# v01.net
KiCad netlist of a schematic drawn in EAGLE
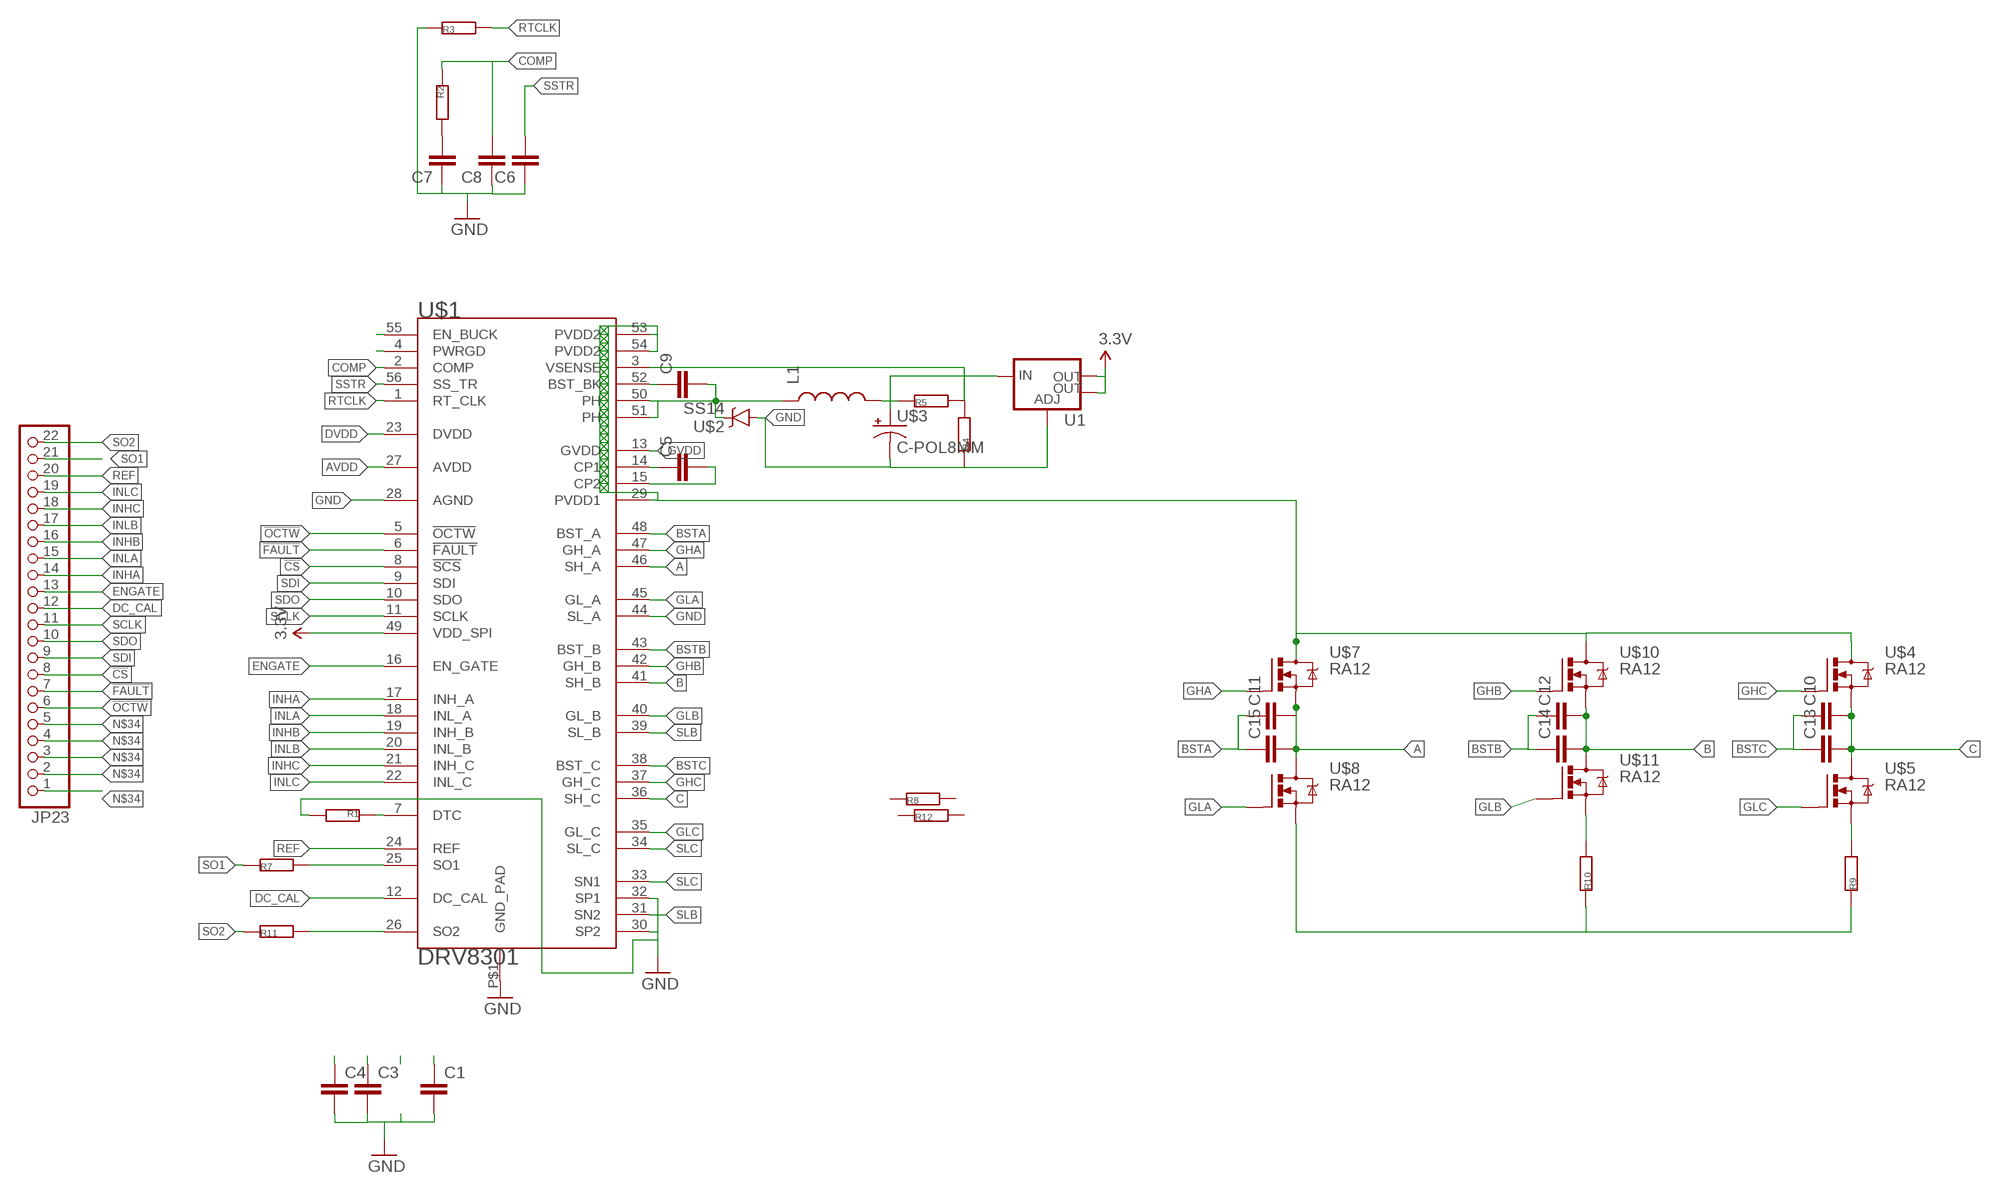
[diagram p0: schematic, sheet 1]

(export (version "E")
  (design (tool "Eeschema 10.0.6"))
  (components
    (comp (ref "C1")
      (value "CC0805")
      (footprint "eagle-import:C0805")
      (libsource (lib "eagle-import") (part "CC0805"))
    )
    (comp (ref "C3")
      (value "CC0805")
      (footprint "eagle-import:C0805")
      (libsource (lib "eagle-import") (part "CC0805"))
    )
    (comp (ref "C4")
      (value "CC0805")
      (footprint "eagle-import:C0805")
      (libsource (lib "eagle-import") (part "CC0805"))
    )
    (comp (ref "C5")
      (value "CC0603")
      (footprint "eagle-import:C0603")
      (libsource (lib "eagle-import") (part "CC0603"))
    )
    (comp (ref "C6")
      (value "CC0805")
      (footprint "eagle-import:C0805")
      (libsource (lib "eagle-import") (part "CC0805"))
    )
    (comp (ref "C7")
      (value "CC0805")
      (footprint "eagle-import:C0805")
      (libsource (lib "eagle-import") (part "CC0805"))
    )
    (comp (ref "C8")
      (value "CC0805")
      (footprint "eagle-import:C0805")
      (libsource (lib "eagle-import") (part "CC0805"))
    )
    (comp (ref "C9")
      (value "CC0603")
      (footprint "eagle-import:C0603")
      (libsource (lib "eagle-import") (part "CC0603"))
    )
    (comp (ref "C10")
      (value "CC0805")
      (footprint "eagle-import:C0805")
      (libsource (lib "eagle-import") (part "CC0805"))
    )
    (comp (ref "C11")
      (value "CC0805")
      (footprint "eagle-import:C0805")
      (libsource (lib "eagle-import") (part "CC0805"))
    )
    (comp (ref "C12")
      (value "CC0805")
      (footprint "eagle-import:C0805")
      (libsource (lib "eagle-import") (part "CC0805"))
    )
    (comp (ref "C13")
      (value "CC0805")
      (footprint "eagle-import:C0805")
      (libsource (lib "eagle-import") (part "CC0805"))
    )
    (comp (ref "C14")
      (value "CC0805")
      (footprint "eagle-import:C0805")
      (libsource (lib "eagle-import") (part "CC0805"))
    )
    (comp (ref "C15")
      (value "CC0805")
      (footprint "eagle-import:C0805")
      (libsource (lib "eagle-import") (part "CC0805"))
    )
    (comp (ref "JP23")
      (value "PINHD-1X22")
      (footprint "eagle-import:1X22")
      (libsource (lib "eagle-import") (part "PINHD-1X22"))
    )
    (comp (ref "L1")
      (value "INDUCTORDR1030")
      (footprint "eagle-import:DR1030")
      (libsource (lib "eagle-import") (part "INDUCTORDR1030"))
    )
    (comp (ref "R1")
      (value "R0603")
      (footprint "eagle-import:0603")
      (libsource (lib "eagle-import") (part "R0603"))
    )
    (comp (ref "R2")
      (value "R0603")
      (footprint "eagle-import:0603")
      (libsource (lib "eagle-import") (part "R0603"))
    )
    (comp (ref "R3")
      (value "R0603")
      (footprint "eagle-import:0603")
      (libsource (lib "eagle-import") (part "R0603"))
    )
    (comp (ref "R4")
      (value "R0603")
      (footprint "eagle-import:0603")
      (libsource (lib "eagle-import") (part "R0603"))
    )
    (comp (ref "R5")
      (value "R0603")
      (footprint "eagle-import:0603")
      (libsource (lib "eagle-import") (part "R0603"))
    )
    (comp (ref "R7")
      (value "R0603")
      (footprint "eagle-import:0603")
      (libsource (lib "eagle-import") (part "R0603"))
    )
    (comp (ref "R8")
      (value "R1206")
      (footprint "eagle-import:R1206")
      (libsource (lib "eagle-import") (part "R1206"))
    )
    (comp (ref "R9")
      (value "R2512")
      (footprint "eagle-import:R2512")
      (libsource (lib "eagle-import") (part "R2512"))
    )
    (comp (ref "R10")
      (value "R2512")
      (footprint "eagle-import:R2512")
      (libsource (lib "eagle-import") (part "R2512"))
    )
    (comp (ref "R11")
      (value "R0603")
      (footprint "eagle-import:0603")
      (libsource (lib "eagle-import") (part "R0603"))
    )
    (comp (ref "R12")
      (value "R1206")
      (footprint "eagle-import:R1206")
      (libsource (lib "eagle-import") (part "R1206"))
    )
    (comp (ref "U$1")
      (value "DRV8301")
      (footprint "eagle-import:HTSSOP56DCA")
      (libsource (lib "eagle-import") (part "DRV8301"))
    )
    (comp (ref "U$2")
      (value "SS14")
      (footprint "eagle-import:SMA-DIODE")
      (libsource (lib "eagle-import") (part "SS14"))
    )
    (comp (ref "U$3")
      (value "C-POL8MM")
      (footprint "eagle-import:PCAP8")
      (libsource (lib "eagle-import") (part "C-POL8MM"))
    )
    (comp (ref "U$4")
      (value "RA12")
      (footprint "eagle-import:POWERPAK_SO8")
      (libsource (lib "eagle-import") (part "RA12"))
    )
    (comp (ref "U$5")
      (value "RA12")
      (footprint "eagle-import:POWERPAK_SO8")
      (libsource (lib "eagle-import") (part "RA12"))
    )
    (comp (ref "U$7")
      (value "RA12")
      (footprint "eagle-import:POWERPAK_SO8")
      (libsource (lib "eagle-import") (part "RA12"))
    )
    (comp (ref "U$8")
      (value "RA12")
      (footprint "eagle-import:POWERPAK_SO8")
      (libsource (lib "eagle-import") (part "RA12"))
    )
    (comp (ref "U$10")
      (value "RA12")
      (footprint "eagle-import:POWERPAK_SO8")
      (libsource (lib "eagle-import") (part "RA12"))
    )
    (comp (ref "U$11")
      (value "RA12")
      (footprint "eagle-import:POWERPAK_SO8")
      (libsource (lib "eagle-import") (part "RA12"))
    )
    (comp (ref "U1")
      (value "V_REG_LM1117SOT223")
      (footprint "eagle-import:SOT223")
      (libsource (lib "eagle-import") (part "V_REG_LM1117SOT223"))
    )
  )
  (nets
    (net (code "1") (name "/~{CS}") (class "Default")
      (node (ref "JP23") (pin "8") (pinfunction "8_8") (pintype "passive"))
      (node (ref "U$1") (pin "8") (pinfunction "~{SCS}_8") (pintype "bidirectional"))
    )
    (net (code "2") (name "/~{FAULT}") (class "Default")
      (node (ref "JP23") (pin "7") (pinfunction "7_7") (pintype "passive"))
      (node (ref "U$1") (pin "6") (pinfunction "~{FAULT}_6") (pintype "bidirectional"))
    )
    (net (code "3") (name "/~{OCTW}") (class "Default")
      (node (ref "JP23") (pin "6") (pinfunction "6_6") (pintype "passive"))
      (node (ref "U$1") (pin "5") (pinfunction "~{OCTW}_5") (pintype "bidirectional"))
    )
    (net (code "4") (name "3.3V") (class "Default")
      (node (ref "U$1") (pin "49") (pinfunction "VDD_SPI_49") (pintype "bidirectional"))
      (node (ref "U1") (pin "2") (pinfunction "OUT_2") (pintype "output"))
      (node (ref "U1") (pin "4") (pinfunction "OUT_4") (pintype "output"))
    )
    (net (code "5") (name "A") (class "Default")
      (node (ref "C11") (pin "2") (pinfunction "2_2") (pintype "passive"))
      (node (ref "C15") (pin "2") (pinfunction "2_2") (pintype "passive"))
      (node (ref "U$1") (pin "46") (pinfunction "SH_A_46") (pintype "bidirectional"))
      (node (ref "U$7") (pin "1") (pinfunction "S_1") (pintype "passive"))
      (node (ref "U$7") (pin "2") (pinfunction "S_2") (pintype "passive"))
      (node (ref "U$7") (pin "3") (pinfunction "S_3") (pintype "passive"))
      (node (ref "U$8") (pin "5") (pinfunction "D_5") (pintype "passive"))
      (node (ref "U$8") (pin "6") (pinfunction "D_6") (pintype "passive"))
      (node (ref "U$8") (pin "7") (pinfunction "D_7") (pintype "passive"))
      (node (ref "U$8") (pin "8") (pinfunction "D_8") (pintype "passive"))
    )
    (net (code "6") (name "AVDD") (class "Default")
      (node (ref "C4") (pin "1") (pinfunction "1_1") (pintype "passive"))
      (node (ref "U$1") (pin "27") (pinfunction "AVDD_27") (pintype "bidirectional"))
    )
    (net (code "7") (name "B") (class "Default")
      (node (ref "C12") (pin "2") (pinfunction "2_2") (pintype "passive"))
      (node (ref "C14") (pin "2") (pinfunction "2_2") (pintype "passive"))
      (node (ref "U$1") (pin "41") (pinfunction "SH_B_41") (pintype "bidirectional"))
      (node (ref "U$10") (pin "1") (pinfunction "S_1") (pintype "passive"))
      (node (ref "U$10") (pin "2") (pinfunction "S_2") (pintype "passive"))
      (node (ref "U$10") (pin "3") (pinfunction "S_3") (pintype "passive"))
      (node (ref "U$11") (pin "5") (pinfunction "D_5") (pintype "passive"))
      (node (ref "U$11") (pin "6") (pinfunction "D_6") (pintype "passive"))
      (node (ref "U$11") (pin "7") (pinfunction "D_7") (pintype "passive"))
      (node (ref "U$11") (pin "8") (pinfunction "D_8") (pintype "passive"))
    )
    (net (code "8") (name "BSTA") (class "Default")
      (node (ref "C11") (pin "1") (pinfunction "1_1") (pintype "passive"))
      (node (ref "C15") (pin "1") (pinfunction "1_1") (pintype "passive"))
      (node (ref "U$1") (pin "48") (pinfunction "BST_A_48") (pintype "bidirectional"))
    )
    (net (code "9") (name "BSTB") (class "Default")
      (node (ref "C12") (pin "1") (pinfunction "1_1") (pintype "passive"))
      (node (ref "C14") (pin "1") (pinfunction "1_1") (pintype "passive"))
      (node (ref "U$1") (pin "43") (pinfunction "BST_B_43") (pintype "bidirectional"))
    )
    (net (code "10") (name "BSTC") (class "Default")
      (node (ref "C10") (pin "1") (pinfunction "1_1") (pintype "passive"))
      (node (ref "C13") (pin "1") (pinfunction "1_1") (pintype "passive"))
      (node (ref "U$1") (pin "38") (pinfunction "BST_C_38") (pintype "bidirectional"))
    )
    (net (code "11") (name "C") (class "Default")
      (node (ref "C10") (pin "2") (pinfunction "2_2") (pintype "passive"))
      (node (ref "C13") (pin "2") (pinfunction "2_2") (pintype "passive"))
      (node (ref "U$1") (pin "36") (pinfunction "SH_C_36") (pintype "bidirectional"))
      (node (ref "U$4") (pin "1") (pinfunction "S_1") (pintype "passive"))
      (node (ref "U$4") (pin "2") (pinfunction "S_2") (pintype "passive"))
      (node (ref "U$4") (pin "3") (pinfunction "S_3") (pintype "passive"))
      (node (ref "U$5") (pin "5") (pinfunction "D_5") (pintype "passive"))
      (node (ref "U$5") (pin "6") (pinfunction "D_6") (pintype "passive"))
      (node (ref "U$5") (pin "7") (pinfunction "D_7") (pintype "passive"))
      (node (ref "U$5") (pin "8") (pinfunction "D_8") (pintype "passive"))
    )
    (net (code "12") (name "COMP") (class "Default")
      (node (ref "C8") (pin "2") (pinfunction "2_2") (pintype "passive"))
      (node (ref "R2") (pin "1") (pinfunction "1_1") (pintype "passive"))
      (node (ref "U$1") (pin "2") (pinfunction "COMP_2") (pintype "bidirectional"))
    )
    (net (code "13") (name "DC_CAL") (class "Default")
      (node (ref "JP23") (pin "12") (pinfunction "12_12") (pintype "passive"))
      (node (ref "U$1") (pin "12") (pinfunction "DC_CAL_12") (pintype "bidirectional"))
    )
    (net (code "14") (name "DVDD") (class "Default")
      (node (ref "C3") (pin "1") (pinfunction "1_1") (pintype "passive"))
      (node (ref "U$1") (pin "23") (pinfunction "DVDD_23") (pintype "bidirectional"))
    )
    (net (code "15") (name "ENGATE") (class "Default")
      (node (ref "JP23") (pin "13") (pinfunction "13_13") (pintype "passive"))
      (node (ref "U$1") (pin "16") (pinfunction "EN_GATE_16") (pintype "bidirectional"))
    )
    (net (code "16") (name "GHA") (class "Default")
      (node (ref "U$1") (pin "47") (pinfunction "GH_A_47") (pintype "bidirectional"))
      (node (ref "U$7") (pin "4") (pinfunction "G_4") (pintype "passive"))
    )
    (net (code "17") (name "GHB") (class "Default")
      (node (ref "U$1") (pin "42") (pinfunction "GH_B_42") (pintype "bidirectional"))
      (node (ref "U$10") (pin "4") (pinfunction "G_4") (pintype "passive"))
    )
    (net (code "18") (name "GHC") (class "Default")
      (node (ref "U$1") (pin "37") (pinfunction "GH_C_37") (pintype "bidirectional"))
      (node (ref "U$4") (pin "4") (pinfunction "G_4") (pintype "passive"))
    )
    (net (code "19") (name "GLA") (class "Default")
      (node (ref "U$1") (pin "45") (pinfunction "GL_A_45") (pintype "bidirectional"))
      (node (ref "U$8") (pin "4") (pinfunction "G_4") (pintype "passive"))
    )
    (net (code "20") (name "GLB") (class "Default")
      (node (ref "U$1") (pin "40") (pinfunction "GL_B_40") (pintype "bidirectional"))
      (node (ref "U$11") (pin "4") (pinfunction "G_4") (pintype "passive"))
    )
    (net (code "21") (name "GLC") (class "Default")
      (node (ref "U$1") (pin "35") (pinfunction "GL_C_35") (pintype "bidirectional"))
      (node (ref "U$5") (pin "4") (pinfunction "G_4") (pintype "passive"))
    )
    (net (code "22") (name "GND") (class "Default")
      (node (ref "C1") (pin "2") (pinfunction "2_2") (pintype "passive"))
      (node (ref "C3") (pin "2") (pinfunction "2_2") (pintype "passive"))
      (node (ref "C4") (pin "2") (pinfunction "2_2") (pintype "passive"))
      (node (ref "C6") (pin "1") (pinfunction "1_1") (pintype "passive"))
      (node (ref "C7") (pin "1") (pinfunction "1_1") (pintype "passive"))
      (node (ref "C8") (pin "1") (pinfunction "1_1") (pintype "passive"))
      (node (ref "R1") (pin "2") (pinfunction "2_2") (pintype "passive"))
      (node (ref "R10") (pin "P$1") (pinfunction "1_P$1") (pintype "passive"))
      (node (ref "R3") (pin "1") (pinfunction "1_1") (pintype "passive"))
      (node (ref "R4") (pin "1") (pinfunction "1_1") (pintype "passive"))
      (node (ref "R9") (pin "P$1") (pinfunction "1_P$1") (pintype "passive"))
      (node (ref "U$1") (pin "28") (pinfunction "AGND_28") (pintype "bidirectional"))
      (node (ref "U$1") (pin "30") (pinfunction "SP2_30") (pintype "bidirectional"))
      (node (ref "U$1") (pin "32") (pinfunction "SP1_32") (pintype "bidirectional"))
      (node (ref "U$1") (pin "44") (pinfunction "SL_A_44") (pintype "bidirectional"))
      (node (ref "U$1") (pin "P$1") (pinfunction "GND_PAD_P$1") (pintype "bidirectional"))
      (node (ref "U$2") (pin "A") (pinfunction "A_A") (pintype "passive"))
      (node (ref "U$3") (pin "P$2") (pinfunction "-_P$2") (pintype "passive"))
      (node (ref "U$8") (pin "1") (pinfunction "S_1") (pintype "passive"))
      (node (ref "U$8") (pin "2") (pinfunction "S_2") (pintype "passive"))
      (node (ref "U$8") (pin "3") (pinfunction "S_3") (pintype "passive"))
      (node (ref "U1") (pin "1") (pinfunction "ADJ_1") (pintype "input"))
    )
    (net (code "23") (name "GVDD") (class "Default")
      (node (ref "C1") (pin "1") (pinfunction "1_1") (pintype "passive"))
      (node (ref "U$1") (pin "13") (pinfunction "GVDD_13") (pintype "bidirectional"))
    )
    (net (code "24") (name "INHA") (class "Default")
      (node (ref "JP23") (pin "14") (pinfunction "14_14") (pintype "passive"))
      (node (ref "U$1") (pin "17") (pinfunction "INH_A_17") (pintype "bidirectional"))
    )
    (net (code "25") (name "INHB") (class "Default")
      (node (ref "JP23") (pin "16") (pinfunction "16_16") (pintype "passive"))
      (node (ref "U$1") (pin "19") (pinfunction "INH_B_19") (pintype "bidirectional"))
    )
    (net (code "26") (name "INHC") (class "Default")
      (node (ref "JP23") (pin "18") (pinfunction "18_18") (pintype "passive"))
      (node (ref "U$1") (pin "21") (pinfunction "INH_C_21") (pintype "bidirectional"))
    )
    (net (code "27") (name "INLA") (class "Default")
      (node (ref "JP23") (pin "15") (pinfunction "15_15") (pintype "passive"))
      (node (ref "U$1") (pin "18") (pinfunction "INL_A_18") (pintype "bidirectional"))
    )
    (net (code "28") (name "INLB") (class "Default")
      (node (ref "JP23") (pin "17") (pinfunction "17_17") (pintype "passive"))
      (node (ref "U$1") (pin "20") (pinfunction "INL_B_20") (pintype "bidirectional"))
    )
    (net (code "29") (name "INLC") (class "Default")
      (node (ref "JP23") (pin "19") (pinfunction "19_19") (pintype "passive"))
      (node (ref "U$1") (pin "22") (pinfunction "INL_C_22") (pintype "bidirectional"))
    )
    (net (code "30") (name "N$34") (class "Default")
      (node (ref "JP23") (pin "1") (pinfunction "1_1") (pintype "passive"))
      (node (ref "JP23") (pin "2") (pinfunction "2_2") (pintype "passive"))
      (node (ref "JP23") (pin "3") (pinfunction "3_3") (pintype "passive"))
      (node (ref "JP23") (pin "4") (pinfunction "4_4") (pintype "passive"))
      (node (ref "JP23") (pin "5") (pinfunction "5_5") (pintype "passive"))
    )
    (net (code "31") (name "Net-(C7-Pad2)") (class "Default")
      (node (ref "C7") (pin "2") (pinfunction "2_2") (pintype "passive"))
      (node (ref "R2") (pin "2") (pinfunction "2_2") (pintype "passive"))
    )
    (net (code "32") (name "Net-(C9-Pad2)") (class "Default")
      (node (ref "C9") (pin "2") (pinfunction "2_2") (pintype "passive"))
      (node (ref "L1") (pin "1") (pinfunction "1_1") (pintype "passive"))
      (node (ref "U$1") (pin "50") (pinfunction "PH_50") (pintype "bidirectional"))
      (node (ref "U$1") (pin "51") (pinfunction "PH_51") (pintype "bidirectional"))
      (node (ref "U$2") (pin "C") (pinfunction "C_C") (pintype "passive"))
    )
    (net (code "33") (name "Net-(U$1-BST_BK)") (class "Default")
      (node (ref "C9") (pin "1") (pinfunction "1_1") (pintype "passive"))
      (node (ref "U$1") (pin "52") (pinfunction "BST_BK_52") (pintype "bidirectional"))
    )
    (net (code "34") (name "Net-(U$1-CP1)") (class "Default")
      (node (ref "C5") (pin "1") (pinfunction "1_1") (pintype "passive"))
      (node (ref "U$1") (pin "14") (pinfunction "CP1_14") (pintype "bidirectional"))
    )
    (net (code "35") (name "Net-(U$1-CP2)") (class "Default")
      (node (ref "C5") (pin "2") (pinfunction "2_2") (pintype "passive"))
      (node (ref "U$1") (pin "15") (pinfunction "CP2_15") (pintype "bidirectional"))
    )
    (net (code "36") (name "Net-(U$1-DTC)") (class "Default")
      (node (ref "R1") (pin "1") (pinfunction "1_1") (pintype "passive"))
      (node (ref "U$1") (pin "7") (pinfunction "DTC_7") (pintype "bidirectional"))
    )
    (net (code "37") (name "Net-(U$1-PVDD1)") (class "Default")
      (node (ref "U$1") (pin "29") (pinfunction "PVDD1_29") (pintype "bidirectional"))
      (node (ref "U$1") (pin "53") (pinfunction "PVDD2_53") (pintype "bidirectional"))
      (node (ref "U$1") (pin "54") (pinfunction "PVDD2_54") (pintype "bidirectional"))
      (node (ref "U$10") (pin "5") (pinfunction "D_5") (pintype "passive"))
      (node (ref "U$10") (pin "6") (pinfunction "D_6") (pintype "passive"))
      (node (ref "U$10") (pin "7") (pinfunction "D_7") (pintype "passive"))
      (node (ref "U$10") (pin "8") (pinfunction "D_8") (pintype "passive"))
      (node (ref "U$4") (pin "5") (pinfunction "D_5") (pintype "passive"))
      (node (ref "U$4") (pin "6") (pinfunction "D_6") (pintype "passive"))
      (node (ref "U$4") (pin "7") (pinfunction "D_7") (pintype "passive"))
      (node (ref "U$4") (pin "8") (pinfunction "D_8") (pintype "passive"))
      (node (ref "U$7") (pin "5") (pinfunction "D_5") (pintype "passive"))
      (node (ref "U$7") (pin "6") (pinfunction "D_6") (pintype "passive"))
      (node (ref "U$7") (pin "7") (pinfunction "D_7") (pintype "passive"))
      (node (ref "U$7") (pin "8") (pinfunction "D_8") (pintype "passive"))
    )
    (net (code "38") (name "Net-(U$1-SO1)") (class "Default")
      (node (ref "R7") (pin "2") (pinfunction "2_2") (pintype "passive"))
      (node (ref "U$1") (pin "25") (pinfunction "SO1_25") (pintype "bidirectional"))
    )
    (net (code "39") (name "Net-(U$1-SO2)") (class "Default")
      (node (ref "R11") (pin "2") (pinfunction "2_2") (pintype "passive"))
      (node (ref "U$1") (pin "26") (pinfunction "SO2_26") (pintype "bidirectional"))
    )
    (net (code "40") (name "Net-(U$1-VSENSE)") (class "Default")
      (node (ref "R4") (pin "2") (pinfunction "2_2") (pintype "passive"))
      (node (ref "R5") (pin "2") (pinfunction "2_2") (pintype "passive"))
      (node (ref "U$1") (pin "3") (pinfunction "VSENSE_3") (pintype "bidirectional"))
    )
    (net (code "41") (name "Net-(U$3-+)") (class "Default")
      (node (ref "L1") (pin "2") (pinfunction "2_2") (pintype "passive"))
      (node (ref "R5") (pin "1") (pinfunction "1_1") (pintype "passive"))
      (node (ref "U$3") (pin "P$1") (pinfunction "+_P$1") (pintype "passive"))
      (node (ref "U1") (pin "3") (pinfunction "IN_3") (pintype "input"))
    )
    (net (code "42") (name "REF") (class "Default")
      (node (ref "JP23") (pin "20") (pinfunction "20_20") (pintype "passive"))
      (node (ref "U$1") (pin "24") (pinfunction "REF_24") (pintype "bidirectional"))
    )
    (net (code "43") (name "RTCLK") (class "Default")
      (node (ref "R3") (pin "2") (pinfunction "2_2") (pintype "passive"))
      (node (ref "U$1") (pin "1") (pinfunction "RT_CLK_1") (pintype "bidirectional"))
    )
    (net (code "44") (name "SCLK") (class "Default")
      (node (ref "JP23") (pin "11") (pinfunction "11_11") (pintype "passive"))
      (node (ref "U$1") (pin "11") (pinfunction "SCLK_11") (pintype "bidirectional"))
    )
    (net (code "45") (name "SDI") (class "Default")
      (node (ref "JP23") (pin "9") (pinfunction "9_9") (pintype "passive"))
      (node (ref "U$1") (pin "9") (pinfunction "SDI_9") (pintype "bidirectional"))
    )
    (net (code "46") (name "SDO") (class "Default")
      (node (ref "JP23") (pin "10") (pinfunction "10_10") (pintype "passive"))
      (node (ref "U$1") (pin "10") (pinfunction "SDO_10") (pintype "bidirectional"))
    )
    (net (code "47") (name "SLB") (class "Default")
      (node (ref "R10") (pin "P$2") (pinfunction "2_P$2") (pintype "passive"))
      (node (ref "U$1") (pin "31") (pinfunction "SN2_31") (pintype "bidirectional"))
      (node (ref "U$1") (pin "39") (pinfunction "SL_B_39") (pintype "bidirectional"))
      (node (ref "U$11") (pin "1") (pinfunction "S_1") (pintype "passive"))
      (node (ref "U$11") (pin "2") (pinfunction "S_2") (pintype "passive"))
      (node (ref "U$11") (pin "3") (pinfunction "S_3") (pintype "passive"))
    )
    (net (code "48") (name "SLC") (class "Default")
      (node (ref "R9") (pin "P$2") (pinfunction "2_P$2") (pintype "passive"))
      (node (ref "U$1") (pin "33") (pinfunction "SN1_33") (pintype "bidirectional"))
      (node (ref "U$1") (pin "34") (pinfunction "SL_C_34") (pintype "bidirectional"))
      (node (ref "U$5") (pin "1") (pinfunction "S_1") (pintype "passive"))
      (node (ref "U$5") (pin "2") (pinfunction "S_2") (pintype "passive"))
      (node (ref "U$5") (pin "3") (pinfunction "S_3") (pintype "passive"))
    )
    (net (code "49") (name "SO1") (class "Default")
      (node (ref "JP23") (pin "21") (pinfunction "21_21") (pintype "passive"))
      (node (ref "R7") (pin "1") (pinfunction "1_1") (pintype "passive"))
    )
    (net (code "50") (name "SO2") (class "Default")
      (node (ref "JP23") (pin "22") (pinfunction "22_22") (pintype "passive"))
      (node (ref "R11") (pin "1") (pinfunction "1_1") (pintype "passive"))
    )
    (net (code "51") (name "SSTR") (class "Default")
      (node (ref "C6") (pin "2") (pinfunction "2_2") (pintype "passive"))
      (node (ref "U$1") (pin "56") (pinfunction "SS_TR_56") (pintype "bidirectional"))
    )
    (net (code "52") (name "unconnected-(R8-Pad1)") (class "Default")
      (node (ref "R8") (pin "1") (pinfunction "1_1") (pintype "passive"))
    )
    (net (code "53") (name "unconnected-(R8-Pad2)") (class "Default")
      (node (ref "R8") (pin "2") (pinfunction "2_2") (pintype "passive"))
    )
    (net (code "54") (name "unconnected-(R12-Pad1)") (class "Default")
      (node (ref "R12") (pin "1") (pinfunction "1_1") (pintype "passive"))
    )
    (net (code "55") (name "unconnected-(R12-Pad2)") (class "Default")
      (node (ref "R12") (pin "2") (pinfunction "2_2") (pintype "passive"))
    )
    (net (code "56") (name "unconnected-(U$1-EN_BUCK-Pad55)") (class "Default")
      (node (ref "U$1") (pin "55") (pinfunction "EN_BUCK_55") (pintype "bidirectional"))
    )
    (net (code "57") (name "unconnected-(U$1-PWRGD-Pad4)") (class "Default")
      (node (ref "U$1") (pin "4") (pinfunction "PWRGD_4") (pintype "bidirectional"))
    )
  )
)
